# NB2_CommonMemory.net
KiCad netlist of a schematic drawn in Altium Designer
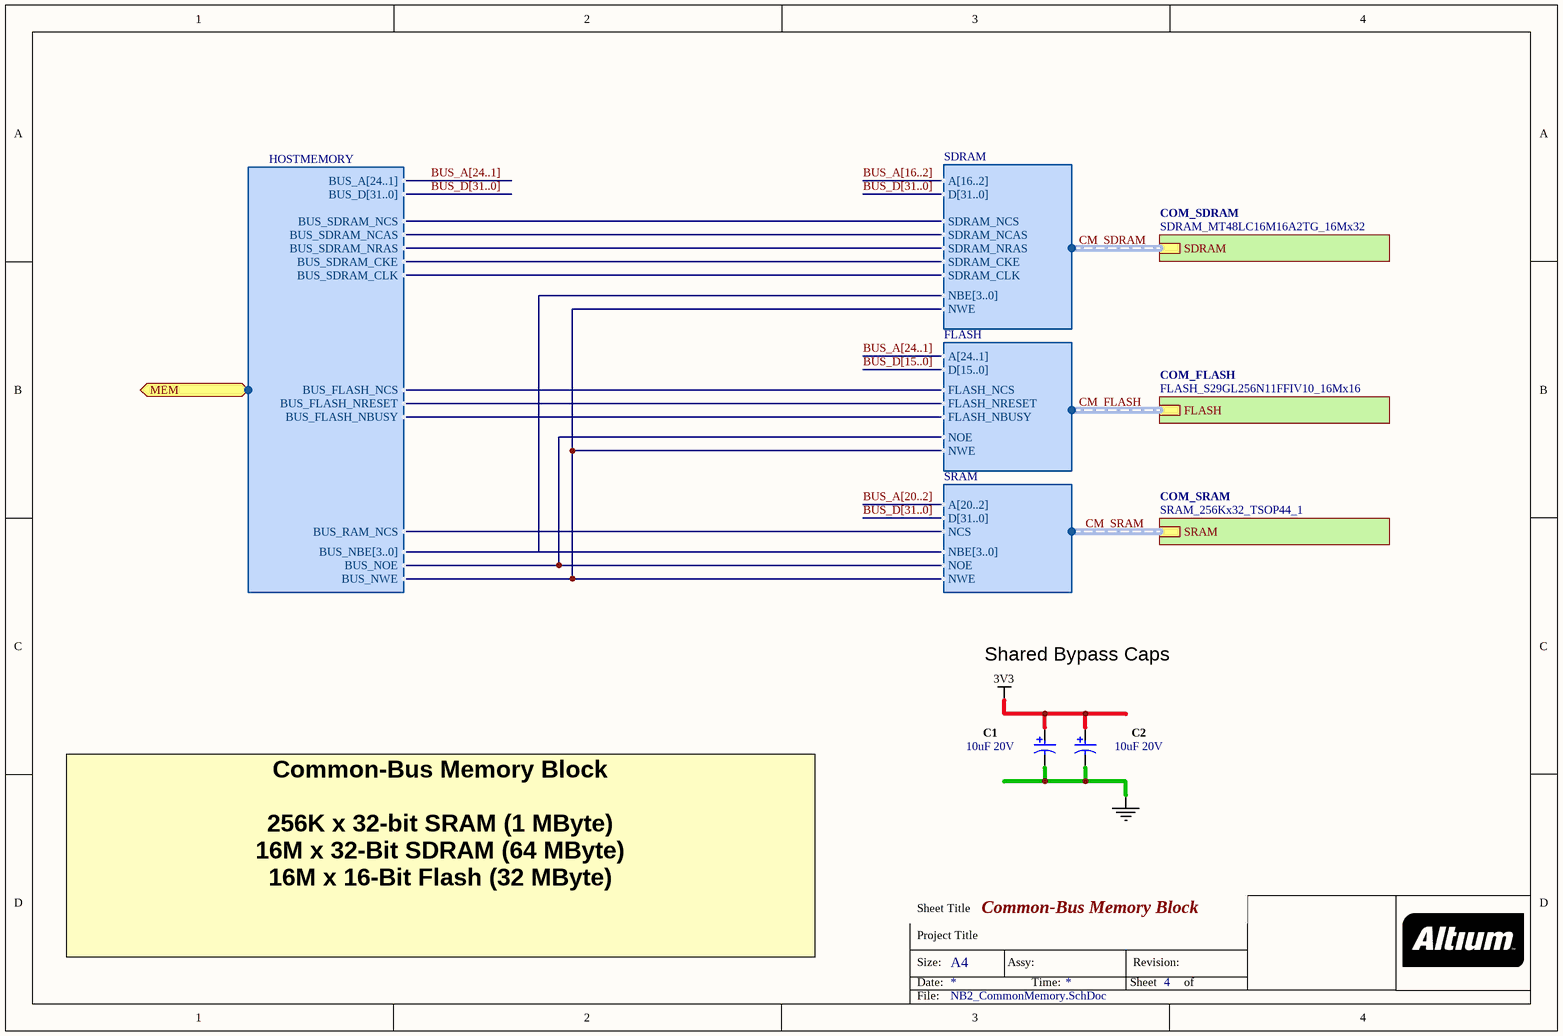
[diagram p0: NB2_CommonMemory.SchDoc]

(export (version "E")
  (design (tool "Eeschema 10.0.6"))
  (components
    (comp (ref "C1")
      (value "10uF 20V")
      (footprint "CAPC3528-STAR")
      (description "Capacitor, Tantalum, 10uF 10% 20V MCCT-B (3528)")
      (fields (field (name "TOLERANCE") "10 %"))
      (libsource (lib "altium-import") (part "root_0_CAP-P_"))
    )
    (comp (ref "C2")
      (value "10uF 20V")
      (footprint "CAPC3528-STAR")
      (description "Capacitor, Tantalum, 10uF 10% 20V MCCT-B (3528)")
      (fields (field (name "TOLERANCE") "10 %"))
      (libsource (lib "altium-import") (part "root_0_CAP-P_"))
    )
  )
  (nets
    (net (code "72") (name "3V3") (class "Default")
      (node (ref "C1") (pin "1") (pinfunction "1_1") (pintype "passive"))
      (node (ref "C2") (pin "1") (pinfunction "1_1") (pintype "passive"))
    )
    (net (code "73") (name "GND") (class "Default")
      (node (ref "C1") (pin "2") (pinfunction "2_2") (pintype "passive"))
      (node (ref "C2") (pin "2") (pinfunction "2_2") (pintype "passive"))
    )
  )
)
